# USB_French_Bar_2.net
KiCad netlist of a schematic drawn in EAGLE
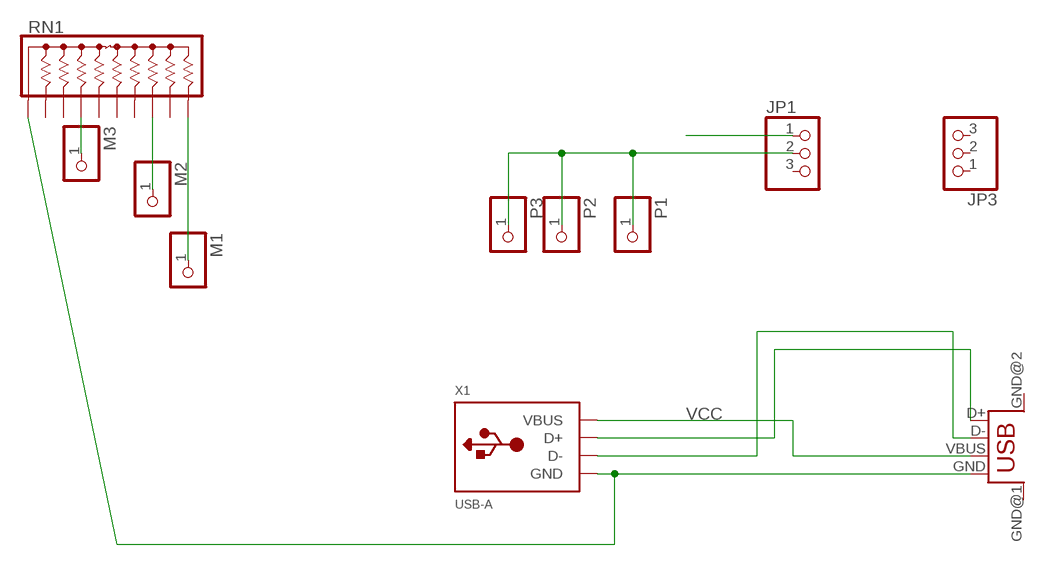
[diagram p0: schematic, sheet 1]

(export (version "E")
  (design (tool "Eeschema 10.0.6"))
  (components
    (comp (ref "JP1")
      (value "PINHD-1X3")
      (footprint "eagle-import:1X03")
      (libsource (lib "eagle-import") (part "PINHD-1X3"))
    )
    (comp (ref "JP3")
      (value "PINHD-1X3")
      (footprint "eagle-import:1X03")
      (libsource (lib "eagle-import") (part "PINHD-1X3"))
    )
    (comp (ref "M1")
      (value "PINHD-1X1")
      (footprint "eagle-import:1X01")
      (libsource (lib "eagle-import") (part "PINHD-1X1"))
    )
    (comp (ref "M2")
      (value "PINHD-1X1")
      (footprint "eagle-import:1X01")
      (libsource (lib "eagle-import") (part "PINHD-1X1"))
    )
    (comp (ref "M3")
      (value "PINHD-1X1")
      (footprint "eagle-import:1X01")
      (libsource (lib "eagle-import") (part "PINHD-1X1"))
    )
    (comp (ref "P1")
      (value "PINHD-1X1")
      (footprint "eagle-import:1X01")
      (libsource (lib "eagle-import") (part "PINHD-1X1"))
    )
    (comp (ref "P2")
      (value "PINHD-1X1")
      (footprint "eagle-import:1X01")
      (libsource (lib "eagle-import") (part "PINHD-1X1"))
    )
    (comp (ref "P3")
      (value "PINHD-1X1")
      (footprint "eagle-import:1X01")
      (libsource (lib "eagle-import") (part "PINHD-1X1"))
    )
    (comp (ref "RN1")
      (value "4610X")
      (footprint "eagle-import:SIP10")
      (libsource (lib "eagle-import") (part "4610X"))
    )
    (comp (ref "U$1")
      (value "USB")
      (footprint "eagle-import:USB-FEMALE-A-PTH")
      (libsource (lib "eagle-import") (part "USB"))
    )
    (comp (ref "X1")
      (value "USB-A")
      (footprint "eagle-import:MOLEX_480371000")
      (libsource (lib "eagle-import") (part "USB-A"))
    )
  )
  (nets
    (net (code "1") (name "/VCC") (class "Default")
      (node (ref "JP1") (pin "1") (pinfunction "1_1") (pintype "passive"))
      (node (ref "U$1") (pin "VBUS") (pinfunction "VBUS_VBUS") (pintype "bidirectional"))
      (node (ref "X1") (pin "1") (pinfunction "VBUS_1") (pintype "power_in"))
    )
    (net (code "2") (name "Net-(JP1-Pad2)") (class "Default")
      (node (ref "JP1") (pin "2") (pinfunction "2_2") (pintype "passive"))
      (node (ref "P1") (pin "1") (pinfunction "1_1") (pintype "passive"))
      (node (ref "P2") (pin "1") (pinfunction "1_1") (pintype "passive"))
      (node (ref "P3") (pin "1") (pinfunction "1_1") (pintype "passive"))
    )
    (net (code "3") (name "Net-(M1-Pad1)") (class "Default")
      (node (ref "M1") (pin "1") (pinfunction "1_1") (pintype "passive"))
      (node (ref "RN1") (pin "10") (pinfunction "10_10") (pintype "passive"))
    )
    (net (code "4") (name "Net-(M2-Pad1)") (class "Default")
      (node (ref "M2") (pin "1") (pinfunction "1_1") (pintype "passive"))
      (node (ref "RN1") (pin "8") (pinfunction "8_8") (pintype "passive"))
    )
    (net (code "5") (name "Net-(M3-Pad1)") (class "Default")
      (node (ref "M3") (pin "1") (pinfunction "1_1") (pintype "passive"))
      (node (ref "RN1") (pin "4") (pinfunction "4_4") (pintype "passive"))
    )
    (net (code "6") (name "Net-(X1-D+)") (class "Default")
      (node (ref "U$1") (pin "D+") (pinfunction "D+_D+") (pintype "bidirectional"))
      (node (ref "X1") (pin "3") (pinfunction "D+_3") (pintype "bidirectional"))
    )
    (net (code "7") (name "Net-(X1-D-)") (class "Default")
      (node (ref "U$1") (pin "D-") (pinfunction "D-_D-") (pintype "bidirectional"))
      (node (ref "X1") (pin "2") (pinfunction "D-_2") (pintype "bidirectional"))
    )
    (net (code "8") (name "Net-(X1-GND)") (class "Default")
      (node (ref "RN1") (pin "1") (pinfunction "1_1") (pintype "passive"))
      (node (ref "U$1") (pin "GND") (pinfunction "GND_GND") (pintype "bidirectional"))
      (node (ref "X1") (pin "4") (pinfunction "GND_4") (pintype "power_in"))
    )
    (net (code "9") (name "unconnected-(JP1-Pad3)") (class "Default")
      (node (ref "JP1") (pin "3") (pinfunction "3_3") (pintype "passive"))
    )
    (net (code "10") (name "unconnected-(JP3-Pad1)") (class "Default")
      (node (ref "JP3") (pin "1") (pinfunction "1_1") (pintype "passive"))
    )
    (net (code "11") (name "unconnected-(JP3-Pad2)") (class "Default")
      (node (ref "JP3") (pin "2") (pinfunction "2_2") (pintype "passive"))
    )
    (net (code "12") (name "unconnected-(JP3-Pad3)") (class "Default")
      (node (ref "JP3") (pin "3") (pinfunction "3_3") (pintype "passive"))
    )
    (net (code "13") (name "unconnected-(RN1-Pad2)") (class "Default")
      (node (ref "RN1") (pin "2") (pinfunction "2_2") (pintype "passive"))
    )
    (net (code "14") (name "unconnected-(RN1-Pad3)") (class "Default")
      (node (ref "RN1") (pin "3") (pinfunction "3_3") (pintype "passive"))
    )
    (net (code "15") (name "unconnected-(RN1-Pad5)") (class "Default")
      (node (ref "RN1") (pin "5") (pinfunction "5_5") (pintype "passive"))
    )
    (net (code "16") (name "unconnected-(RN1-Pad6)") (class "Default")
      (node (ref "RN1") (pin "6") (pinfunction "6_6") (pintype "passive"))
    )
    (net (code "17") (name "unconnected-(RN1-Pad7)") (class "Default")
      (node (ref "RN1") (pin "7") (pinfunction "7_7") (pintype "passive"))
    )
    (net (code "18") (name "unconnected-(RN1-Pad9)") (class "Default")
      (node (ref "RN1") (pin "9") (pinfunction "9_9") (pintype "passive"))
    )
    (net (code "19") (name "unconnected-(U$1-GND-PadGND@1)") (class "Default")
      (node (ref "U$1") (pin "GND@1") (pinfunction "GND_GND@1") (pintype "bidirectional"))
    )
    (net (code "20") (name "unconnected-(U$1-GND-PadGND@2)") (class "Default")
      (node (ref "U$1") (pin "GND@2") (pinfunction "GND_GND@2") (pintype "bidirectional"))
    )
  )
)
